# 24VRegulatorKhaled.net
KiCad netlist of a schematic drawn in Altium Designer
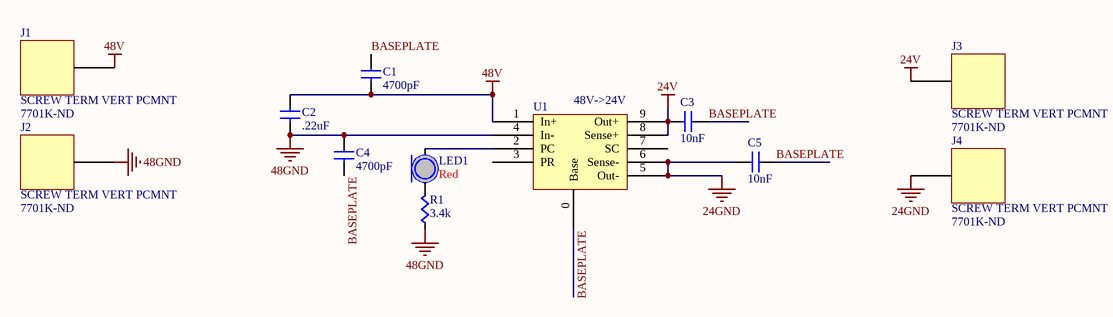
[diagram p0: 24VRegulatorKhaled.SchDoc]

(export (version "E")
  (design (tool "Eeschema 10.0.6"))
  (components
    (comp (ref "C1")
      (value "4700pF")
      (footprint "Kemet PME271Y447MR30")
      (description "Kemet PME271Y447MR30/P271HL472M250A")
      (fields (field (name "Comment") "Cap"))
      (libsource (lib "SubjuGator8") (part "Cap"))
    )
    (comp (ref "C2")
      (value ".22uF")
      (footprint "CAP2225")
      (fields (field (name "Comment") "Cap"))
      (libsource (lib "SubjuGator8") (part "Cap"))
    )
    (comp (ref "C3")
      (value "10nF")
      (footprint "CAP2225")
      (fields (field (name "Comment") "Cap"))
      (libsource (lib "SubjuGator8") (part "Cap"))
    )
    (comp (ref "C4")
      (value "4700pF")
      (footprint "Kemet PME271Y447MR30")
      (description "Kemet PME271Y447MR30/P271HL472M250A")
      (fields (field (name "Comment") "Cap"))
      (libsource (lib "SubjuGator8") (part "Cap"))
    )
    (comp (ref "C5")
      (value "10nF")
      (footprint "CAP2225")
      (fields (field (name "Comment") "Cap"))
      (libsource (lib "SubjuGator8") (part "Cap"))
    )
    (comp (ref "J1")
      (value "SCREW TERM VERT PCMNT")
      (footprint "SCREW TERM SINGLE VERT")
      (description "Keystone Electronics 7701")
      (fields (field (name "SUPPLIER PART NUMBER 1") "7701K-ND"))
      (libsource (lib "") (part "SCREW TERM VERT PCMNT_1"))
    )
    (comp (ref "J2")
      (value "SCREW TERM VERT PCMNT")
      (footprint "SCREW TERM SINGLE VERT")
      (description "Keystone Electronics 7701")
      (fields (field (name "SUPPLIER PART NUMBER 1") "7701K-ND"))
      (libsource (lib "") (part "SCREW TERM VERT PCMNT_1"))
    )
    (comp (ref "J3")
      (value "SCREW TERM VERT PCMNT")
      (footprint "SCREW TERM SINGLE VERT")
      (description "Keystone Electronics 7701")
      (fields (field (name "SUPPLIER PART NUMBER 1") "7701K-ND"))
      (libsource (lib "Connectors") (part "SCREW TERM VERT PCMNT"))
    )
    (comp (ref "J4")
      (value "SCREW TERM VERT PCMNT")
      (footprint "SCREW TERM SINGLE VERT")
      (description "Keystone Electronics 7701")
      (fields (field (name "SUPPLIER PART NUMBER 1") "7701K-ND"))
      (libsource (lib "Connectors") (part "SCREW TERM VERT PCMNT"))
    )
    (comp (ref "LED1")
      (value "LED")
      (footprint "LED0603")
      (fields (field (name "COLOR") "Red"))
      (libsource (lib "SubjuGator8") (part "LED"))
    )
    (comp (ref "R1")
      (value "3.4k")
      (footprint "RES0603")
      (fields (field (name "Comment") "Res"))
      (libsource (lib "SubjuGator8") (part "Res"))
    )
    (comp (ref "U1")
      (value "48V->24V")
      (footprint "FASTRAK_MINI_ONBOARD_MOUNT")
      (description "CONVERTER MOD DC/DC 24V 250W")
      (libsource (lib "SubjuGator8") (part "V48B24C250BL"))
    )
  )
  (nets
    (net (code "1") (name "/BASEPLATE") (class "Default")
      (node (ref "C1") (pin "1") (pinfunction "A_1") (pintype "passive"))
      (node (ref "C3") (pin "2") (pinfunction "B_2") (pintype "passive"))
      (node (ref "C4") (pin "2") (pinfunction "B_2") (pintype "passive"))
      (node (ref "C5") (pin "2") (pinfunction "B_2") (pintype "passive"))
      (node (ref "U1") (pin "0") (pinfunction "Base_0") (pintype "passive"))
    )
    (net (code "2") (name "24GND") (class "Default")
      (node (ref "C5") (pin "1") (pinfunction "A_1") (pintype "passive"))
      (node (ref "J4") (pin "0") (pinfunction "1_0") (pintype "passive"))
      (node (ref "U1") (pin "5") (pinfunction "Out-_5") (pintype "passive"))
      (node (ref "U1") (pin "6") (pinfunction "Sense-_6") (pintype "passive"))
    )
    (net (code "3") (name "24V") (class "Default")
      (node (ref "C3") (pin "1") (pinfunction "A_1") (pintype "passive"))
      (node (ref "J3") (pin "0") (pinfunction "1_0") (pintype "passive"))
      (node (ref "U1") (pin "8") (pinfunction "Sense+_8") (pintype "passive"))
      (node (ref "U1") (pin "9") (pinfunction "Out+_9") (pintype "passive"))
    )
    (net (code "4") (name "48GND") (class "Default")
      (node (ref "C2") (pin "2") (pinfunction "B_2") (pintype "passive"))
      (node (ref "C4") (pin "1") (pinfunction "A_1") (pintype "passive"))
      (node (ref "J2") (pin "0") (pinfunction "1_0") (pintype "passive"))
      (node (ref "R1") (pin "2") (pinfunction "B_2") (pintype "passive"))
      (node (ref "U1") (pin "4") (pinfunction "In-_4") (pintype "passive"))
    )
    (net (code "5") (name "48V") (class "Default")
      (node (ref "C1") (pin "2") (pinfunction "B_2") (pintype "passive"))
      (node (ref "C2") (pin "1") (pinfunction "A_1") (pintype "passive"))
      (node (ref "J1") (pin "0") (pinfunction "1_0") (pintype "passive"))
      (node (ref "U1") (pin "1") (pinfunction "In+_1") (pintype "passive"))
    )
    (net (code "6") (name "Net-(R1-A)") (class "Default")
      (node (ref "LED1") (pin "C") (pinfunction "C_C") (pintype "passive"))
      (node (ref "R1") (pin "1") (pinfunction "A_1") (pintype "passive"))
    )
    (net (code "7") (name "Net-(U1-PC)") (class "Default")
      (node (ref "LED1") (pin "A") (pinfunction "A_A") (pintype "passive"))
      (node (ref "U1") (pin "2") (pinfunction "PC_2") (pintype "passive"))
    )
    (net (code "8") (name "unconnected-(U1-PR-Pad3)") (class "Default")
      (node (ref "U1") (pin "3") (pinfunction "PR_3") (pintype "passive"))
    )
    (net (code "9") (name "unconnected-(U1-SC-Pad7)") (class "Default")
      (node (ref "U1") (pin "7") (pinfunction "SC_7") (pintype "passive"))
    )
  )
)
